# DDR3B.net
KiCad netlist of a schematic drawn in Altium Designer
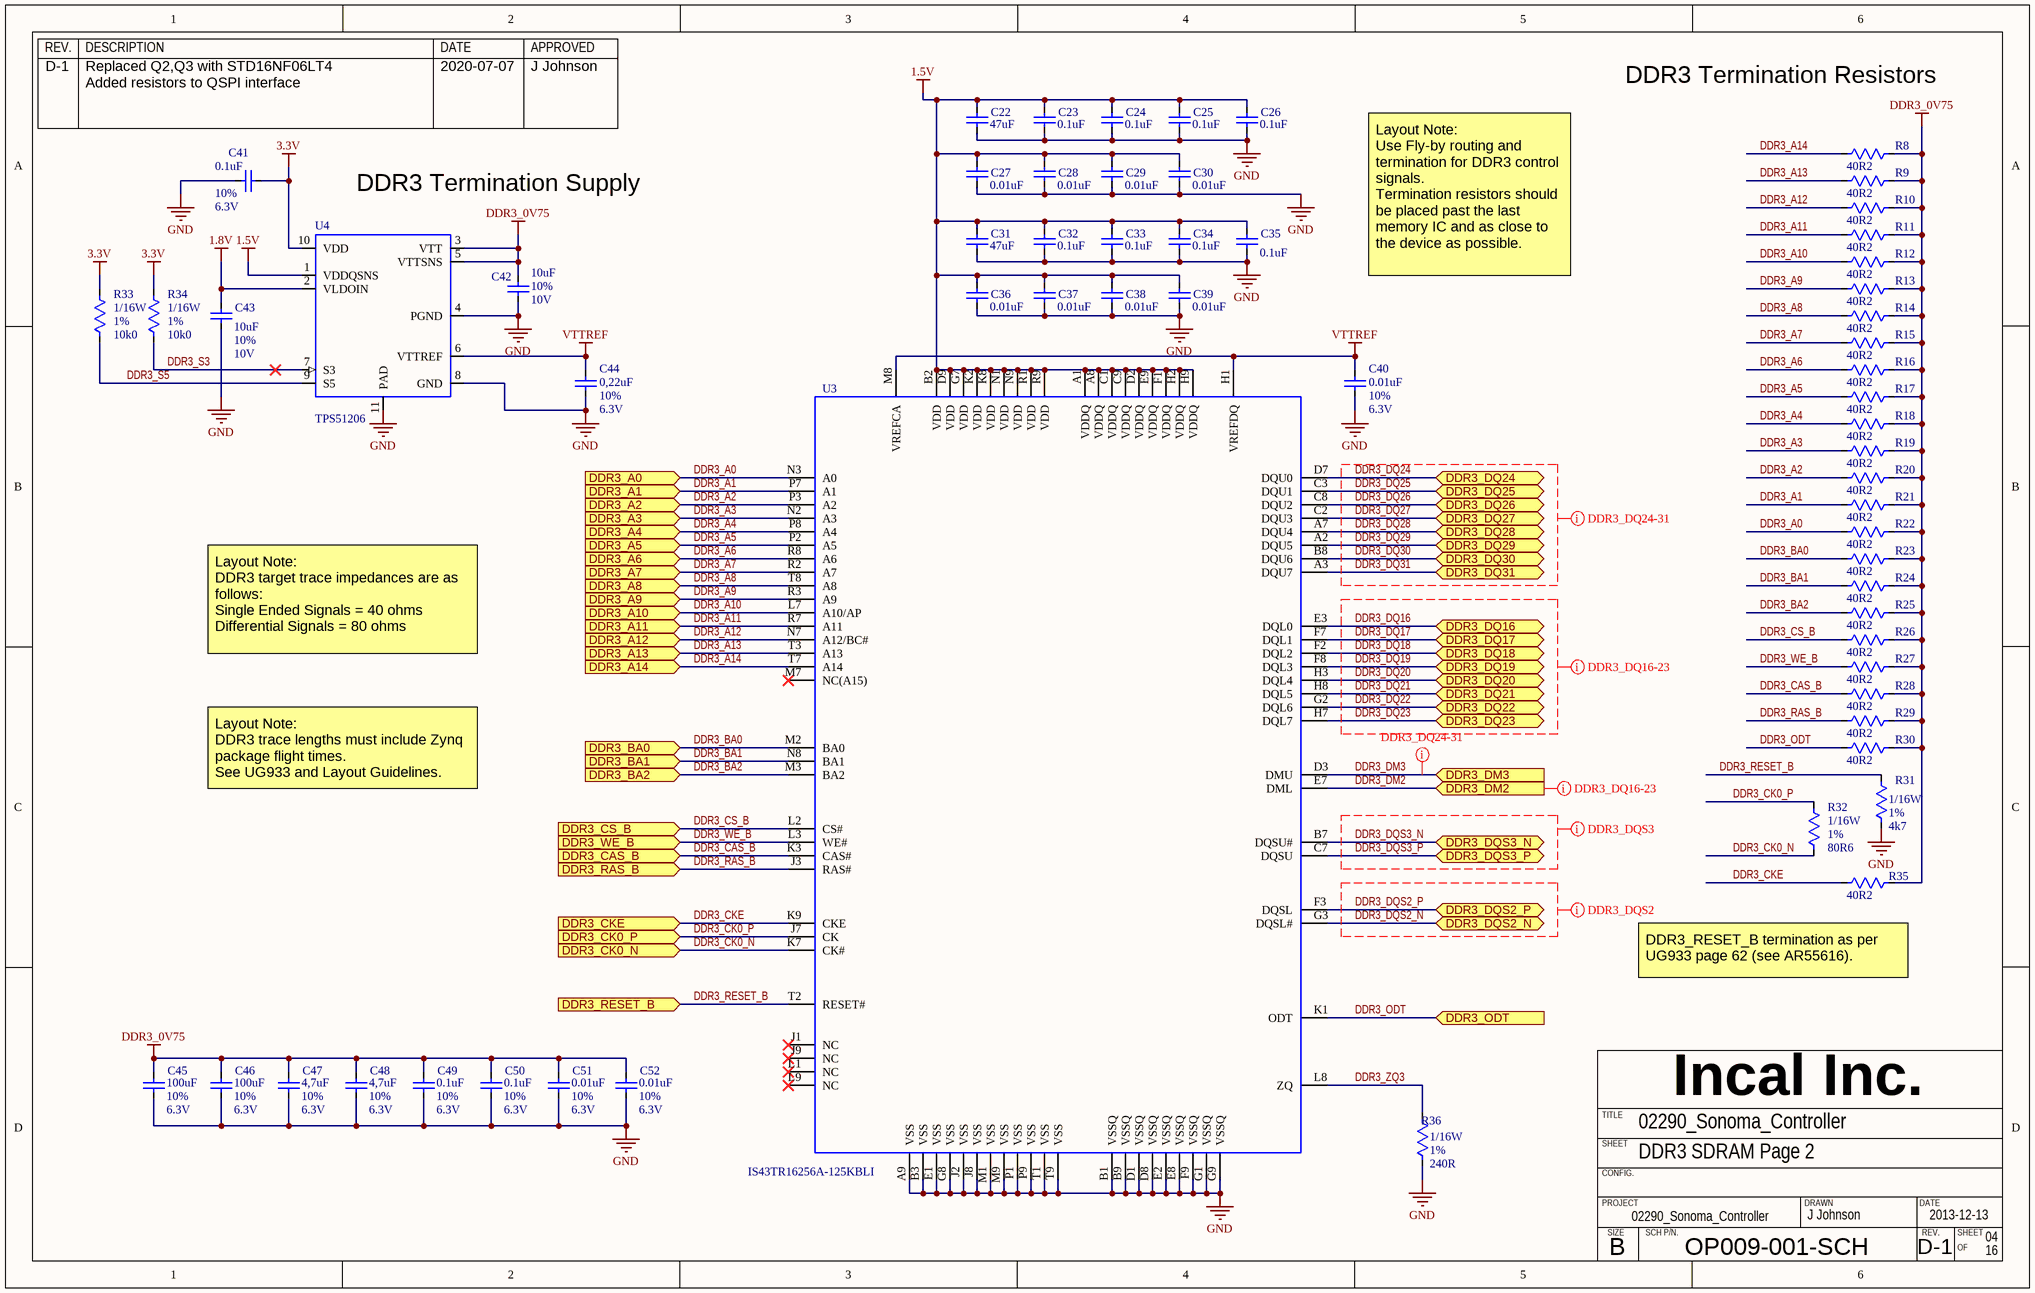
[diagram p0: DDR3B.SchDoc]

(export (version "E")
  (design (tool "Eeschema 10.0.6"))
  (components
    (comp (ref "C22")
      (value "47uF")
      (footprint "CAPC2013X125N")
      (description "Capacitor ceramic, X5R, 47uF, 6.3V, 20%, -55 to +85 C,")
      (fields (field (name "TOLERANCE") "20%") (field (name "VOLTAGE") "6.3V"))
      (libsource (lib "parts") (part "CAPACITOR_NP_TYPE1"))
    )
    (comp (ref "C23")
      (value "0.1uF")
      (footprint "CAPC0603X33N")
      (description "Capacitor ceramic, X5R, 0.1uF, 6.3V, 10%, -55 to +125 C, EIA0201")
      (fields (field (name "TOLERANCE") "10%") (field (name "VOLTAGE") "6.3V"))
      (libsource (lib "parts") (part "CAPACITOR_NP_TYPE1"))
    )
    (comp (ref "C24")
      (value "0.1uF")
      (footprint "CAPC0603X33N")
      (description "Capacitor ceramic, X5R, 0.1uF, 6.3V, 10%, -55 to +125 C, EIA0201")
      (fields (field (name "TOLERANCE") "10%") (field (name "VOLTAGE") "6.3V"))
      (libsource (lib "parts") (part "CAPACITOR_NP_TYPE1"))
    )
    (comp (ref "C25")
      (value "0.1uF")
      (footprint "CAPC0603X33N")
      (description "Capacitor ceramic, X5R, 0.1uF, 6.3V, 10%, -55 to +125 C, EIA0201")
      (fields (field (name "TOLERANCE") "10%") (field (name "VOLTAGE") "6.3V"))
      (libsource (lib "parts") (part "CAPACITOR_NP_TYPE1"))
    )
    (comp (ref "C26")
      (value "0.1uF")
      (footprint "CAPC0603X33N")
      (description "Capacitor ceramic, X5R, 0.1uF, 6.3V, 10%, -55 to +125 C, EIA0201")
      (fields (field (name "TOLERANCE") "10%") (field (name "VOLTAGE") "6.3V"))
      (libsource (lib "parts") (part "CAPACITOR_NP_TYPE1"))
    )
    (comp (ref "C27")
      (value "0.01uF")
      (footprint "CAPC0603X33N")
      (description "Capacitor ceramic, X5R, 0.01uF, 6.3V, 10%, -55 to +125 C, EIA0201")
      (fields (field (name "TOLERANCE") "10%") (field (name "VOLTAGE") "6.3V"))
      (libsource (lib "parts") (part "CAPACITOR_NP_TYPE1"))
    )
    (comp (ref "C28")
      (value "0.01uF")
      (footprint "CAPC0603X33N")
      (description "Capacitor ceramic, X5R, 0.01uF, 6.3V, 10%, -55 to +125 C, EIA0201")
      (fields (field (name "TOLERANCE") "10%") (field (name "VOLTAGE") "6.3V"))
      (libsource (lib "parts") (part "CAPACITOR_NP_TYPE1"))
    )
    (comp (ref "C29")
      (value "0.01uF")
      (footprint "CAPC0603X33N")
      (description "Capacitor ceramic, X5R, 0.01uF, 6.3V, 10%, -55 to +125 C, EIA0201")
      (fields (field (name "TOLERANCE") "10%") (field (name "VOLTAGE") "6.3V"))
      (libsource (lib "parts") (part "CAPACITOR_NP_TYPE1"))
    )
    (comp (ref "C30")
      (value "0.01uF")
      (footprint "CAPC0603X33N")
      (description "Capacitor ceramic, X5R, 0.01uF, 6.3V, 10%, -55 to +125 C, EIA0201")
      (fields (field (name "TOLERANCE") "10%") (field (name "VOLTAGE") "6.3V"))
      (libsource (lib "parts") (part "CAPACITOR_NP_TYPE1"))
    )
    (comp (ref "C31")
      (value "47uF")
      (footprint "CAPC2013X125N")
      (description "Capacitor ceramic, X5R, 47uF, 6.3V, 20%, -55 to +85 C,")
      (fields (field (name "TOLERANCE") "20%") (field (name "VOLTAGE") "6.3V"))
      (libsource (lib "parts") (part "CAPACITOR_NP_TYPE1"))
    )
    (comp (ref "C32")
      (value "0.1uF")
      (footprint "CAPC0603X33N")
      (description "Capacitor ceramic, X5R, 0.1uF, 6.3V, 10%, -55 to +125 C, EIA0201")
      (fields (field (name "TOLERANCE") "10%") (field (name "VOLTAGE") "6.3V"))
      (libsource (lib "parts") (part "CAPACITOR_NP_TYPE1"))
    )
    (comp (ref "C33")
      (value "0.1uF")
      (footprint "CAPC0603X33N")
      (description "Capacitor ceramic, X5R, 0.1uF, 6.3V, 10%, -55 to +125 C, EIA0201")
      (fields (field (name "TOLERANCE") "10%") (field (name "VOLTAGE") "6.3V"))
      (libsource (lib "parts") (part "CAPACITOR_NP_TYPE1"))
    )
    (comp (ref "C34")
      (value "0.1uF")
      (footprint "CAPC0603X33N")
      (description "Capacitor ceramic, X5R, 0.1uF, 6.3V, 10%, -55 to +125 C, EIA0201")
      (fields (field (name "TOLERANCE") "10%") (field (name "VOLTAGE") "6.3V"))
      (libsource (lib "parts") (part "CAPACITOR_NP_TYPE1"))
    )
    (comp (ref "C35")
      (value "0.1uF")
      (footprint "CAPC0603X33N")
      (description "Capacitor ceramic, X5R, 0.1uF, 6.3V, 10%, -55 to +125 C, EIA0201")
      (fields (field (name "TOLERANCE") "10%") (field (name "VOLTAGE") "6.3V"))
      (libsource (lib "parts") (part "CAPACITOR_NP_TYPE1"))
    )
    (comp (ref "C36")
      (value "0.01uF")
      (footprint "CAPC0603X33N")
      (description "Capacitor ceramic, X5R, 0.01uF, 6.3V, 10%, -55 to +125 C, EIA0201")
      (fields (field (name "TOLERANCE") "10%") (field (name "VOLTAGE") "6.3V"))
      (libsource (lib "parts") (part "CAPACITOR_NP_TYPE1"))
    )
    (comp (ref "C37")
      (value "0.01uF")
      (footprint "CAPC0603X33N")
      (description "Capacitor ceramic, X5R, 0.01uF, 6.3V, 10%, -55 to +125 C, EIA0201")
      (fields (field (name "TOLERANCE") "10%") (field (name "VOLTAGE") "6.3V"))
      (libsource (lib "parts") (part "CAPACITOR_NP_TYPE1"))
    )
    (comp (ref "C38")
      (value "0.01uF")
      (footprint "CAPC0603X33N")
      (description "Capacitor ceramic, X5R, 0.01uF, 6.3V, 10%, -55 to +125 C, EIA0201")
      (fields (field (name "TOLERANCE") "10%") (field (name "VOLTAGE") "6.3V"))
      (libsource (lib "parts") (part "CAPACITOR_NP_TYPE1"))
    )
    (comp (ref "C39")
      (value "0.01uF")
      (footprint "CAPC0603X33N")
      (description "Capacitor ceramic, X5R, 0.01uF, 6.3V, 10%, -55 to +125 C, EIA0201")
      (fields (field (name "TOLERANCE") "10%") (field (name "VOLTAGE") "6.3V"))
      (libsource (lib "parts") (part "CAPACITOR_NP_TYPE1"))
    )
    (comp (ref "C40")
      (value "0.01uF")
      (footprint "CAPC0603X33N")
      (description "Capacitor ceramic, X5R, 0.01uF, 6.3V, 10%, -55 to +125 C, EIA0201")
      (fields
        (field (name "TOLERANCE") "10%")
        (field (name "VOLTAGE") "6.3V")
        (field (name "Comment") "CAPACITOR_NP_TYPE1")
      )
      (libsource (lib "parts") (part "CAPACITOR_NP_TYPE1"))
    )
    (comp (ref "C41")
      (value "0.1uF")
      (footprint "CAPC0603X33N")
      (description "Capacitor ceramic, X5R, 0.1uF, 6.3V, 10%, -55 to +125 C, EIA0201")
      (fields
        (field (name "TOLERANCE") "10%")
        (field (name "VOLTAGE") "6.3V")
        (field (name "Comment") "CAPACITOR_NP_TYPE1")
      )
      (libsource (lib "parts") (part "CAPACITOR_NP_TYPE1"))
    )
    (comp (ref "C42")
      (value "10uF")
      (footprint "CAPC1608X38N")
      (description "Capacitor ceramic, X5R, 10uF, 10V, 10%, -55 to +85 C, EIA0603")
      (fields
        (field (name "TOLERANCE") "10%")
        (field (name "VOLTAGE") "10V")
        (field (name "Comment") "CAPACITOR_NP_TYPE1")
      )
      (libsource (lib "parts") (part "CAPACITOR_NP_TYPE1"))
    )
    (comp (ref "C43")
      (value "10uF")
      (footprint "CAPC1608X38N")
      (description "Capacitor ceramic, X5R, 10uF, 10V, 10%, -55 to +85 C, EIA0603")
      (fields
        (field (name "TOLERANCE") "10%")
        (field (name "VOLTAGE") "10V")
        (field (name "Comment") "CAPACITOR_NP_TYPE1")
      )
      (libsource (lib "parts") (part "CAPACITOR_NP_TYPE1"))
    )
    (comp (ref "C44")
      (value "0,22uF")
      (footprint "CAPC1005X55N")
      (description "Capacitor ceramic, X5R, 0.22uF, 6.3V, 10%, -55 to +85 C, EIA0402")
      (fields
        (field (name "TOLERANCE") "10%")
        (field (name "VOLTAGE") "6.3V")
        (field (name "Comment") "CAPACITOR_NP_TYPE1")
      )
      (libsource (lib "parts") (part "CAPACITOR_NP_TYPE1"))
    )
    (comp (ref "C45")
      (value "100uF")
      (footprint "CAPC3225X250N")
      (description "Capacitor ceramic, X5R, 100uF, 6.3V, 10%, -55 to +85 C, EIA1210")
      (fields
        (field (name "TOLERANCE") "10%")
        (field (name "VOLTAGE") "6.3V")
        (field (name "Comment") "CAPACITOR_NP_TYPE1")
      )
      (libsource (lib "parts") (part "CAPACITOR_NP_TYPE1"))
    )
    (comp (ref "C46")
      (value "100uF")
      (footprint "CAPC3225X250N")
      (description "Capacitor ceramic, X5R, 100uF, 6.3V, 10%, -55 to +85 C, EIA1210")
      (fields
        (field (name "TOLERANCE") "10%")
        (field (name "VOLTAGE") "6.3V")
        (field (name "Comment") "CAPACITOR_NP_TYPE1")
      )
      (libsource (lib "parts") (part "CAPACITOR_NP_TYPE1"))
    )
    (comp (ref "C47")
      (value "4,7uF")
      (footprint "CAPC1005X33N")
      (description "Capacitor ceramic, X5R, 4,7uF, 6.3V, 10%, -55 to +85 C, EIA0402")
      (fields
        (field (name "TOLERANCE") "10%")
        (field (name "VOLTAGE") "6.3V")
        (field (name "Comment") "CAPACITOR_NP_TYPE1")
      )
      (libsource (lib "parts") (part "CAPACITOR_NP_TYPE1"))
    )
    (comp (ref "C48")
      (value "4,7uF")
      (footprint "CAPC1005X33N")
      (description "Capacitor ceramic, X5R, 4,7uF, 6.3V, 10%, -55 to +85 C, EIA0402")
      (fields
        (field (name "TOLERANCE") "10%")
        (field (name "VOLTAGE") "6.3V")
        (field (name "Comment") "CAPACITOR_NP_TYPE1")
      )
      (libsource (lib "parts") (part "CAPACITOR_NP_TYPE1"))
    )
    (comp (ref "C49")
      (value "0.1uF")
      (footprint "CAPC0603X33N")
      (description "Capacitor ceramic, X5R, 0.1uF, 6.3V, 10%, -55 to +125 C, EIA0201")
      (fields
        (field (name "TOLERANCE") "10%")
        (field (name "VOLTAGE") "6.3V")
        (field (name "Comment") "CAPACITOR_NP_TYPE1")
      )
      (libsource (lib "parts") (part "CAPACITOR_NP_TYPE1"))
    )
    (comp (ref "C50")
      (value "0.1uF")
      (footprint "CAPC0603X33N")
      (description "Capacitor ceramic, X5R, 0.1uF, 6.3V, 10%, -55 to +125 C, EIA0201")
      (fields
        (field (name "TOLERANCE") "10%")
        (field (name "VOLTAGE") "6.3V")
        (field (name "Comment") "CAPACITOR_NP_TYPE1")
      )
      (libsource (lib "parts") (part "CAPACITOR_NP_TYPE1"))
    )
    (comp (ref "C51")
      (value "0.01uF")
      (footprint "CAPC0603X33N")
      (description "Capacitor ceramic, X5R, 0.01uF, 6.3V, 10%, -55 to +125 C, EIA0201")
      (fields
        (field (name "TOLERANCE") "10%")
        (field (name "VOLTAGE") "6.3V")
        (field (name "Comment") "CAPACITOR_NP_TYPE1")
      )
      (libsource (lib "parts") (part "CAPACITOR_NP_TYPE1"))
    )
    (comp (ref "C52")
      (value "0.01uF")
      (footprint "CAPC0603X33N")
      (description "Capacitor ceramic, X5R, 0.01uF, 6.3V, 10%, -55 to +125 C, EIA0201")
      (fields
        (field (name "TOLERANCE") "10%")
        (field (name "VOLTAGE") "6.3V")
        (field (name "Comment") "CAPACITOR_NP_TYPE1")
      )
      (libsource (lib "parts") (part "CAPACITOR_NP_TYPE1"))
    )
    (comp (ref "R8")
      (value "40R2")
      (footprint "RESC1005X33N")
      (description "Resistor, 40R2, 1/16W, 1%, -50 to +155 C, EIA0402, EIA(M)1005")
      (fields (field (name "VOLTAGE") "50V") (field (name "POWER") "1/16W"))
      (libsource (lib "parts") (part "RESISTOR_TYPE1"))
    )
    (comp (ref "R9")
      (value "40R2")
      (footprint "RESC1005X33N")
      (description "Resistor, 40R2, 1/16W, 1%, -50 to +155 C, EIA0402, EIA(M)1005")
      (fields (field (name "VOLTAGE") "50V") (field (name "POWER") "1/16W"))
      (libsource (lib "parts") (part "RESISTOR_TYPE1"))
    )
    (comp (ref "R10")
      (value "40R2")
      (footprint "RESC1005X33N")
      (description "Resistor, 40R2, 1/16W, 1%, -50 to +155 C, EIA0402, EIA(M)1005")
      (fields (field (name "VOLTAGE") "50V") (field (name "POWER") "1/16W"))
      (libsource (lib "parts") (part "RESISTOR_TYPE1"))
    )
    (comp (ref "R11")
      (value "40R2")
      (footprint "RESC1005X33N")
      (description "Resistor, 40R2, 1/16W, 1%, -50 to +155 C, EIA0402, EIA(M)1005")
      (fields (field (name "VOLTAGE") "50V") (field (name "POWER") "1/16W"))
      (libsource (lib "parts") (part "RESISTOR_TYPE1"))
    )
    (comp (ref "R12")
      (value "40R2")
      (footprint "RESC1005X33N")
      (description "Resistor, 40R2, 1/16W, 1%, -50 to +155 C, EIA0402, EIA(M)1005")
      (fields (field (name "VOLTAGE") "50V") (field (name "POWER") "1/16W"))
      (libsource (lib "parts") (part "RESISTOR_TYPE1"))
    )
    (comp (ref "R13")
      (value "40R2")
      (footprint "RESC1005X33N")
      (description "Resistor, 40R2, 1/16W, 1%, -50 to +155 C, EIA0402, EIA(M)1005")
      (fields (field (name "VOLTAGE") "50V") (field (name "POWER") "1/16W"))
      (libsource (lib "parts") (part "RESISTOR_TYPE1"))
    )
    (comp (ref "R14")
      (value "40R2")
      (footprint "RESC1005X33N")
      (description "Resistor, 40R2, 1/16W, 1%, -50 to +155 C, EIA0402, EIA(M)1005")
      (fields (field (name "VOLTAGE") "50V") (field (name "POWER") "1/16W"))
      (libsource (lib "parts") (part "RESISTOR_TYPE1"))
    )
    (comp (ref "R15")
      (value "40R2")
      (footprint "RESC1005X33N")
      (description "Resistor, 40R2, 1/16W, 1%, -50 to +155 C, EIA0402, EIA(M)1005")
      (fields (field (name "VOLTAGE") "50V") (field (name "POWER") "1/16W"))
      (libsource (lib "parts") (part "RESISTOR_TYPE1"))
    )
    (comp (ref "R16")
      (value "40R2")
      (footprint "RESC1005X33N")
      (description "Resistor, 40R2, 1/16W, 1%, -50 to +155 C, EIA0402, EIA(M)1005")
      (fields (field (name "VOLTAGE") "50V") (field (name "POWER") "1/16W"))
      (libsource (lib "parts") (part "RESISTOR_TYPE1"))
    )
    (comp (ref "R17")
      (value "40R2")
      (footprint "RESC1005X33N")
      (description "Resistor, 40R2, 1/16W, 1%, -50 to +155 C, EIA0402, EIA(M)1005")
      (fields (field (name "VOLTAGE") "50V") (field (name "POWER") "1/16W"))
      (libsource (lib "parts") (part "RESISTOR_TYPE1"))
    )
    (comp (ref "R18")
      (value "40R2")
      (footprint "RESC1005X33N")
      (description "Resistor, 40R2, 1/16W, 1%, -50 to +155 C, EIA0402, EIA(M)1005")
      (fields (field (name "VOLTAGE") "50V") (field (name "POWER") "1/16W"))
      (libsource (lib "parts") (part "RESISTOR_TYPE1"))
    )
    (comp (ref "R19")
      (value "40R2")
      (footprint "RESC1005X33N")
      (description "Resistor, 40R2, 1/16W, 1%, -50 to +155 C, EIA0402, EIA(M)1005")
      (fields (field (name "VOLTAGE") "50V") (field (name "POWER") "1/16W"))
      (libsource (lib "parts") (part "RESISTOR_TYPE1"))
    )
    (comp (ref "R20")
      (value "40R2")
      (footprint "RESC1005X33N")
      (description "Resistor, 40R2, 1/16W, 1%, -50 to +155 C, EIA0402, EIA(M)1005")
      (fields (field (name "VOLTAGE") "50V") (field (name "POWER") "1/16W"))
      (libsource (lib "parts") (part "RESISTOR_TYPE1"))
    )
    (comp (ref "R21")
      (value "40R2")
      (footprint "RESC1005X33N")
      (description "Resistor, 40R2, 1/16W, 1%, -50 to +155 C, EIA0402, EIA(M)1005")
      (fields (field (name "VOLTAGE") "50V") (field (name "POWER") "1/16W"))
      (libsource (lib "parts") (part "RESISTOR_TYPE1"))
    )
    (comp (ref "R22")
      (value "40R2")
      (footprint "RESC1005X33N")
      (description "Resistor, 40R2, 1/16W, 1%, -50 to +155 C, EIA0402, EIA(M)1005")
      (fields (field (name "VOLTAGE") "50V") (field (name "POWER") "1/16W"))
      (libsource (lib "parts") (part "RESISTOR_TYPE1"))
    )
    (comp (ref "R23")
      (value "40R2")
      (footprint "RESC1005X33N")
      (description "Resistor, 40R2, 1/16W, 1%, -50 to +155 C, EIA0402, EIA(M)1005")
      (fields (field (name "VOLTAGE") "50V") (field (name "POWER") "1/16W"))
      (libsource (lib "parts") (part "RESISTOR_TYPE1"))
    )
    (comp (ref "R24")
      (value "40R2")
      (footprint "RESC1005X33N")
      (description "Resistor, 40R2, 1/16W, 1%, -50 to +155 C, EIA0402, EIA(M)1005")
      (fields (field (name "VOLTAGE") "50V") (field (name "POWER") "1/16W"))
      (libsource (lib "parts") (part "RESISTOR_TYPE1"))
    )
    (comp (ref "R25")
      (value "40R2")
      (footprint "RESC1005X33N")
      (description "Resistor, 40R2, 1/16W, 1%, -50 to +155 C, EIA0402, EIA(M)1005")
      (fields (field (name "VOLTAGE") "50V") (field (name "POWER") "1/16W"))
      (libsource (lib "parts") (part "RESISTOR_TYPE1"))
    )
    (comp (ref "R26")
      (value "40R2")
      (footprint "RESC1005X33N")
      (description "Resistor, 40R2, 1/16W, 1%, -50 to +155 C, EIA0402, EIA(M)1005")
      (fields (field (name "VOLTAGE") "50V") (field (name "POWER") "1/16W"))
      (libsource (lib "parts") (part "RESISTOR_TYPE1"))
    )
    (comp (ref "R27")
      (value "40R2")
      (footprint "RESC1005X33N")
      (description "Resistor, 40R2, 1/16W, 1%, -50 to +155 C, EIA0402, EIA(M)1005")
      (fields (field (name "VOLTAGE") "50V") (field (name "POWER") "1/16W"))
      (libsource (lib "parts") (part "RESISTOR_TYPE1"))
    )
    (comp (ref "R28")
      (value "40R2")
      (footprint "RESC1005X33N")
      (description "Resistor, 40R2, 1/16W, 1%, -50 to +155 C, EIA0402, EIA(M)1005")
      (fields (field (name "VOLTAGE") "50V") (field (name "POWER") "1/16W"))
      (libsource (lib "parts") (part "RESISTOR_TYPE1"))
    )
    (comp (ref "R29")
      (value "40R2")
      (footprint "RESC1005X33N")
      (description "Resistor, 40R2, 1/16W, 1%, -50 to +155 C, EIA0402, EIA(M)1005")
      (fields (field (name "VOLTAGE") "50V") (field (name "POWER") "1/16W"))
      (libsource (lib "parts") (part "RESISTOR_TYPE1"))
    )
    (comp (ref "R30")
      (value "40R2")
      (footprint "RESC1005X33N")
      (description "Resistor, 40R2, 1/16W, 1%, -50 to +155 C, EIA0402, EIA(M)1005")
      (fields (field (name "VOLTAGE") "50V") (field (name "POWER") "1/16W"))
      (libsource (lib "parts") (part "RESISTOR_TYPE1"))
    )
    (comp (ref "R31")
      (value "4k7")
      (footprint "RESC1005X33N")
      (description "Resistor, 4k7, 1/16W, 1%, -55 to +155 C, EIA0402")
      (fields (field (name "VOLTAGE") "50V") (field (name "POWER") "1/16W") (field (name "TOLERANCE") "1%"))
      (libsource (lib "parts") (part "RESISTOR_TYPE1"))
    )
    (comp (ref "R32")
      (value "80R6")
      (footprint "RESC1005X33N")
      (description "Resistor, 80R6, 1/16W, 1%, -50 to +155 C, EIA0402, EIA(M)1005")
      (fields (field (name "VOLTAGE") "50V") (field (name "POWER") "1/16W") (field (name "TOLERANCE") "1%"))
      (libsource (lib "parts") (part "RESISTOR_TYPE1"))
    )
    (comp (ref "R33")
      (value "10k0")
      (footprint "RESC1005X33N")
      (description "Resistor, 10k0, 1/16W, 1%, -55 to +155 C, EIA0402")
      (fields (field (name "VOLTAGE") "50V") (field (name "POWER") "1/16W") (field (name "TOLERANCE") "1%"))
      (libsource (lib "parts") (part "RESISTOR_TYPE1"))
    )
    (comp (ref "R34")
      (value "10k0")
      (footprint "RESC1005X33N")
      (description "Resistor, 10k0, 1/16W, 1%, -55 to +155 C, EIA0402")
      (fields (field (name "VOLTAGE") "50V") (field (name "POWER") "1/16W") (field (name "TOLERANCE") "1%"))
      (libsource (lib "parts") (part "RESISTOR_TYPE1"))
    )
    (comp (ref "R35")
      (value "40R2")
      (footprint "RESC1005X33N")
      (description "Resistor, 40R2, 1/16W, 1%, -50 to +155 C, EIA0402, EIA(M)1005")
      (fields (field (name "VOLTAGE") "50V") (field (name "POWER") "1/16W"))
      (libsource (lib "parts") (part "RESISTOR_TYPE1"))
    )
    (comp (ref "R36")
      (value "240R")
      (footprint "RESC1005X33N")
      (description "Resistor, 240R, 1/16W, 1%, -50 to +155 C, EIA0402, EIA(M)1005")
      (fields (field (name "VOLTAGE") "50V") (field (name "POWER") "1/16W") (field (name "TOLERANCE") "1%"))
      (libsource (lib "parts") (part "RESISTOR_TYPE1"))
    )
    (comp (ref "U3")
      (value "IS43TR16256A-125KBLI")
      (footprint "BGA96C80P6X16_900X1300X120")
      (description "DDR3 SDRAM, 512Mx8, 256Mx16 4Gb")
      (libsource (lib "parts") (part "IS43TR16256A-125KBLI"))
    )
    (comp (ref "U4")
      (value "TPS51206")
      (footprint "DFN40P200X200X75-11N")
      (description "DDR Termination Regulator, -40 to +85 C")
      (fields (field (name "VOLTAGE") "3.3V or 5V"))
      (libsource (lib "parts") (part "TPS51206"))
    )
  )
  (nets
    (net (code "1") (name "/DDR3_A0") (class "Default")
      (node (ref "R22") (pin "2") (pinfunction "2_2") (pintype "passive"))
      (node (ref "U3") (pin "N3") (pinfunction "A0_N3") (pintype "passive"))
    )
    (net (code "2") (name "/DDR3_A1") (class "Default")
      (node (ref "R21") (pin "2") (pinfunction "2_2") (pintype "passive"))
      (node (ref "U3") (pin "P7") (pinfunction "A1_P7") (pintype "passive"))
    )
    (net (code "3") (name "/DDR3_A2") (class "Default")
      (node (ref "R20") (pin "2") (pinfunction "2_2") (pintype "passive"))
      (node (ref "U3") (pin "P3") (pinfunction "A2_P3") (pintype "passive"))
    )
    (net (code "4") (name "/DDR3_A3") (class "Default")
      (node (ref "R19") (pin "2") (pinfunction "2_2") (pintype "passive"))
      (node (ref "U3") (pin "N2") (pinfunction "A3_N2") (pintype "passive"))
    )
    (net (code "5") (name "/DDR3_A4") (class "Default")
      (node (ref "R18") (pin "2") (pinfunction "2_2") (pintype "passive"))
      (node (ref "U3") (pin "P8") (pinfunction "A4_P8") (pintype "passive"))
    )
    (net (code "6") (name "/DDR3_A5") (class "Default")
      (node (ref "R17") (pin "2") (pinfunction "2_2") (pintype "passive"))
      (node (ref "U3") (pin "P2") (pinfunction "A5_P2") (pintype "passive"))
    )
    (net (code "7") (name "/DDR3_A6") (class "Default")
      (node (ref "R16") (pin "2") (pinfunction "2_2") (pintype "passive"))
      (node (ref "U3") (pin "R8") (pinfunction "A6_R8") (pintype "passive"))
    )
    (net (code "8") (name "/DDR3_A7") (class "Default")
      (node (ref "R15") (pin "2") (pinfunction "2_2") (pintype "passive"))
      (node (ref "U3") (pin "R2") (pinfunction "A7_R2") (pintype "passive"))
    )
    (net (code "9") (name "/DDR3_A8") (class "Default")
      (node (ref "R14") (pin "2") (pinfunction "2_2") (pintype "passive"))
      (node (ref "U3") (pin "T8") (pinfunction "A8_T8") (pintype "passive"))
    )
    (net (code "10") (name "/DDR3_A9") (class "Default")
      (node (ref "R13") (pin "2") (pinfunction "2_2") (pintype "passive"))
      (node (ref "U3") (pin "R3") (pinfunction "A9_R3") (pintype "passive"))
    )
    (net (code "11") (name "/DDR3_A10") (class "Default")
      (node (ref "R12") (pin "2") (pinfunction "2_2") (pintype "passive"))
      (node (ref "U3") (pin "L7") (pinfunction "A10/AP_L7") (pintype "passive"))
    )
    (net (code "12") (name "/DDR3_A11") (class "Default")
      (node (ref "R11") (pin "2") (pinfunction "2_2") (pintype "passive"))
      (node (ref "U3") (pin "R7") (pinfunction "A11_R7") (pintype "passive"))
    )
    (net (code "13") (name "/DDR3_A12") (class "Default")
      (node (ref "R10") (pin "2") (pinfunction "2_2") (pintype "passive"))
      (node (ref "U3") (pin "N7") (pinfunction "A12/BC#_N7") (pintype "passive"))
    )
    (net (code "14") (name "/DDR3_A13") (class "Default")
      (node (ref "R9") (pin "2") (pinfunction "2_2") (pintype "passive"))
      (node (ref "U3") (pin "T3") (pinfunction "A13_T3") (pintype "passive"))
    )
    (net (code "15") (name "/DDR3_A14") (class "Default")
      (node (ref "R8") (pin "2") (pinfunction "2_2") (pintype "passive"))
      (node (ref "U3") (pin "T7") (pinfunction "A14_T7") (pintype "passive"))
    )
    (net (code "16") (name "/DDR3_BA0") (class "Default")
      (node (ref "R23") (pin "2") (pinfunction "2_2") (pintype "passive"))
      (node (ref "U3") (pin "M2") (pinfunction "BA0_M2") (pintype "passive"))
    )
    (net (code "17") (name "/DDR3_BA1") (class "Default")
      (node (ref "R24") (pin "2") (pinfunction "2_2") (pintype "passive"))
      (node (ref "U3") (pin "N8") (pinfunction "BA1_N8") (pintype "passive"))
    )
    (net (code "18") (name "/DDR3_BA2") (class "Default")
      (node (ref "R25") (pin "2") (pinfunction "2_2") (pintype "passive"))
      (node (ref "U3") (pin "M3") (pinfunction "BA2_M3") (pintype "passive"))
    )
    (net (code "19") (name "/DDR3_CAS_B") (class "Default")
      (node (ref "R28") (pin "2") (pinfunction "2_2") (pintype "passive"))
      (node (ref "U3") (pin "K3") (pinfunction "CAS#_K3") (pintype "passive"))
    )
    (net (code "20") (name "/DDR3_CK0_N") (class "Default")
      (node (ref "R32") (pin "1") (pinfunction "1_1") (pintype "passive"))
      (node (ref "U3") (pin "K7") (pinfunction "CK#_K7") (pintype "passive"))
    )
    (net (code "21") (name "/DDR3_CK0_P") (class "Default")
      (node (ref "R32") (pin "2") (pinfunction "2_2") (pintype "passive"))
      (node (ref "U3") (pin "J7") (pinfunction "CK_J7") (pintype "passive"))
    )
    (net (code "22") (name "/DDR3_CKE") (class "Default")
      (node (ref "R35") (pin "2") (pinfunction "2_2") (pintype "passive"))
      (node (ref "U3") (pin "K9") (pinfunction "CKE_K9") (pintype "passive"))
    )
    (net (code "23") (name "/DDR3_CS_B") (class "Default")
      (node (ref "R26") (pin "2") (pinfunction "2_2") (pintype "passive"))
      (node (ref "U3") (pin "L2") (pinfunction "CS#_L2") (pintype "passive"))
    )
    (net (code "24") (name "/DDR3_DM2") (class "Default")
      (node (ref "U3") (pin "E7") (pinfunction "DML_E7") (pintype "passive"))
    )
    (net (code "25") (name "/DDR3_DM3") (class "Default")
      (node (ref "U3") (pin "D3") (pinfunction "DMU_D3") (pintype "passive"))
    )
    (net (code "26") (name "/DDR3_DQ16") (class "Default")
      (node (ref "U3") (pin "E3") (pinfunction "DQL0_E3") (pintype "passive"))
    )
    (net (code "27") (name "/DDR3_DQ17") (class "Default")
      (node (ref "U3") (pin "F7") (pinfunction "DQL1_F7") (pintype "passive"))
    )
    (net (code "28") (name "/DDR3_DQ18") (class "Default")
      (node (ref "U3") (pin "F2") (pinfunction "DQL2_F2") (pintype "passive"))
    )
    (net (code "29") (name "/DDR3_DQ19") (class "Default")
      (node (ref "U3") (pin "F8") (pinfunction "DQL3_F8") (pintype "passive"))
    )
    (net (code "30") (name "/DDR3_DQ20") (class "Default")
      (node (ref "U3") (pin "H3") (pinfunction "DQL4_H3") (pintype "passive"))
    )
    (net (code "31") (name "/DDR3_DQ21") (class "Default")
      (node (ref "U3") (pin "H8") (pinfunction "DQL5_H8") (pintype "passive"))
    )
    (net (code "32") (name "/DDR3_DQ22") (class "Default")
      (node (ref "U3") (pin "G2") (pinfunction "DQL6_G2") (pintype "passive"))
    )
    (net (code "33") (name "/DDR3_DQ23") (class "Default")
      (node (ref "U3") (pin "H7") (pinfunction "DQL7_H7") (pintype "passive"))
    )
    (net (code "34") (name "/DDR3_DQ24") (class "Default")
      (node (ref "U3") (pin "D7") (pinfunction "DQU0_D7") (pintype "passive"))
    )
    (net (code "35") (name "/DDR3_DQ25") (class "Default")
      (node (ref "U3") (pin "C3") (pinfunction "DQU1_C3") (pintype "passive"))
    )
    (net (code "36") (name "/DDR3_DQ26") (class "Default")
      (node (ref "U3") (pin "C8") (pinfunction "DQU2_C8") (pintype "passive"))
    )
    (net (code "37") (name "/DDR3_DQ27") (class "Default")
      (node (ref "U3") (pin "C2") (pinfunction "DQU3_C2") (pintype "passive"))
    )
    (net (code "38") (name "/DDR3_DQ28") (class "Default")
      (node (ref "U3") (pin "A7") (pinfunction "DQU4_A7") (pintype "passive"))
    )
    (net (code "39") (name "/DDR3_DQ29") (class "Default")
      (node (ref "U3") (pin "A2") (pinfunction "DQU5_A2") (pintype "passive"))
    )
    (net (code "40") (name "/DDR3_DQ30") (class "Default")
      (node (ref "U3") (pin "B8") (pinfunction "DQU6_B8") (pintype "passive"))
    )
    (net (code "41") (name "/DDR3_DQ31") (class "Default")
      (node (ref "U3") (pin "A3") (pinfunction "DQU7_A3") (pintype "passive"))
    )
    (net (code "42") (name "/DDR3_DQS2_N") (class "Default")
      (node (ref "U3") (pin "G3") (pinfunction "DQSL#_G3") (pintype "passive"))
    )
    (net (code "43") (name "/DDR3_DQS2_P") (class "Default")
      (node (ref "U3") (pin "F3") (pinfunction "DQSL_F3") (pintype "passive"))
    )
    (net (code "44") (name "/DDR3_DQS3_N") (class "Default")
      (node (ref "U3") (pin "B7") (pinfunction "DQSU#_B7") (pintype "passive"))
    )
    (net (code "45") (name "/DDR3_DQS3_P") (class "Default")
      (node (ref "U3") (pin "C7") (pinfunction "DQSU_C7") (pintype "passive"))
    )
    (net (code "46") (name "/DDR3_ODT") (class "Default")
      (node (ref "R30") (pin "2") (pinfunction "2_2") (pintype "passive"))
      (node (ref "U3") (pin "K1") (pinfunction "ODT_K1") (pintype "passive"))
    )
    (net (code "47") (name "/DDR3_RAS_B") (class "Default")
      (node (ref "R29") (pin "2") (pinfunction "2_2") (pintype "passive"))
      (node (ref "U3") (pin "J3") (pinfunction "RAS#_J3") (pintype "passive"))
    )
    (net (code "48") (name "/DDR3_RESET_B") (class "Default")
      (node (ref "R31") (pin "1") (pinfunction "1_1") (pintype "passive"))
      (node (ref "U3") (pin "T2") (pinfunction "RESET#_T2") (pintype "passive"))
    )
    (net (code "49") (name "/DDR3_S3") (class "Default")
      (node (ref "R34") (pin "2") (pinfunction "2_2") (pintype "passive"))
      (node (ref "U4") (pin "7") (pinfunction "S3_7") (pintype "input"))
    )
    (net (code "50") (name "/DDR3_S5") (class "Default")
      (node (ref "R33") (pin "2") (pinfunction "2_2") (pintype "passive"))
      (node (ref "U4") (pin "9") (pinfunction "S5_9") (pintype "passive"))
    )
    (net (code "51") (name "/DDR3_WE_B") (class "Default")
      (node (ref "R27") (pin "2") (pinfunction "2_2") (pintype "passive"))
      (node (ref "U3") (pin "L3") (pinfunction "WE#_L3") (pintype "passive"))
    )
    (net (code "52") (name "/DDR3_ZQ3") (class "Default")
      (node (ref "R36") (pin "2") (pinfunction "2_2") (pintype "passive"))
      (node (ref "U3") (pin "L8") (pinfunction "ZQ_L8") (pintype "passive"))
    )
    (net (code "53") (name "1.5V") (class "Default")
      (node (ref "C22") (pin "1") (pinfunction "1_1") (pintype "passive"))
      (node (ref "C23") (pin "1") (pinfunction "1_1") (pintype "passive"))
      (node (ref "C24") (pin "1") (pinfunction "1_1") (pintype "passive"))
      (node (ref "C25") (pin "1") (pinfunction "1_1") (pintype "passive"))
      (node (ref "C26") (pin "1") (pinfunction "1_1") (pintype "passive"))
      (node (ref "C27") (pin "1") (pinfunction "1_1") (pintype "passive"))
      (node (ref "C28") (pin "1") (pinfunction "1_1") (pintype "passive"))
      (node (ref "C29") (pin "1") (pinfunction "1_1") (pintype "passive"))
      (node (ref "C30") (pin "1") (pinfunction "1_1") (pintype "passive"))
      (node (ref "C31") (pin "1") (pinfunction "1_1") (pintype "passive"))
      (node (ref "C32") (pin "1") (pinfunction "1_1") (pintype "passive"))
      (node (ref "C33") (pin "1") (pinfunction "1_1") (pintype "passive"))
      (node (ref "C34") (pin "1") (pinfunction "1_1") (pintype "passive"))
      (node (ref "C35") (pin "1") (pinfunction "1_1") (pintype "passive"))
      (node (ref "C36") (pin "1") (pinfunction "1_1") (pintype "passive"))
      (node (ref "C37") (pin "1") (pinfunction "1_1") (pintype "passive"))
      (node (ref "C38") (pin "1") (pinfunction "1_1") (pintype "passive"))
      (node (ref "C39") (pin "1") (pinfunction "1_1") (pintype "passive"))
      (node (ref "U3") (pin "A1") (pinfunction "VDDQ_A1") (pintype "passive"))
      (node (ref "U3") (pin "A8") (pinfunction "VDDQ_A8") (pintype "passive"))
      (node (ref "U3") (pin "B2") (pinfunction "VDD_B2") (pintype "passive"))
      (node (ref "U3") (pin "C1") (pinfunction "VDDQ_C1") (pintype "passive"))
      (node (ref "U3") (pin "C9") (pinfunction "VDDQ_C9") (pintype "passive"))
      (node (ref "U3") (pin "D2") (pinfunction "VDDQ_D2") (pintype "passive"))
      (node (ref "U3") (pin "D9") (pinfunction "VDD_D9") (pintype "passive"))
      (node (ref "U3") (pin "E9") (pinfunction "VDDQ_E9") (pintype "passive"))
      (node (ref "U3") (pin "F1") (pinfunction "VDDQ_F1") (pintype "passive"))
      (node (ref "U3") (pin "G7") (pinfunction "VDD_G7") (pintype "passive"))
      (node (ref "U3") (pin "H2") (pinfunction "VDDQ_H2") (pintype "passive"))
      (node (ref "U3") (pin "H9") (pinfunction "VDDQ_H9") (pintype "passive"))
      (node (ref "U3") (pin "K2") (pinfunction "VDD_K2") (pintype "passive"))
      (node (ref "U3") (pin "K8") (pinfunction "VDD_K8") (pintype "passive"))
      (node (ref "U3") (pin "N1") (pinfunction "VDD_N1") (pintype "passive"))
      (node (ref "U3") (pin "N9") (pinfunction "VDD_N9") (pintype "passive"))
      (node (ref "U3") (pin "R1") (pinfunction "VDD_R1") (pintype "passive"))
      (node (ref "U3") (pin "R9") (pinfunction "VDD_R9") (pintype "passive"))
      (node (ref "U4") (pin "1") (pinfunction "VDDQSNS_1") (pintype "power_in"))
    )
    (net (code "54") (name "1.8V") (class "Default")
      (node (ref "C43") (pin "1") (pinfunction "1_1") (pintype "passive"))
      (node (ref "U4") (pin "2") (pinfunction "VLDOIN_2") (pintype "power_in"))
    )
    (net (code "55") (name "3.3V") (class "Default")
      (node (ref "C41") (pin "1") (pinfunction "1_1") (pintype "passive"))
      (node (ref "R33") (pin "1") (pinfunction "1_1") (pintype "passive"))
      (node (ref "R34") (pin "1") (pinfunction "1_1") (pintype "passive"))
      (node (ref "U4") (pin "10") (pinfunction "VDD_10") (pintype "power_in"))
    )
    (net (code "56") (name "DDR3_0V75") (class "Default")
      (node (ref "C42") (pin "1") (pinfunction "1_1") (pintype "passive"))
      (node (ref "C45") (pin "1") (pinfunction "1_1") (pintype "passive"))
      (node (ref "C46") (pin "1") (pinfunction "1_1") (pintype "passive"))
      (node (ref "C47") (pin "1") (pinfunction "1_1") (pintype "passive"))
      (node (ref "C48") (pin "1") (pinfunction "1_1") (pintype "passive"))
      (node (ref "C49") (pin "1") (pinfunction "1_1") (pintype "passive"))
      (node (ref "C50") (pin "1") (pinfunction "1_1") (pintype "passive"))
      (node (ref "C51") (pin "1") (pinfunction "1_1") (pintype "passive"))
      (node (ref "C52") (pin "1") (pinfunction "1_1") (pintype "passive"))
      (node (ref "R10") (pin "1") (pinfunction "1_1") (pintype "passive"))
      (node (ref "R11") (pin "1") (pinfunction "1_1") (pintype "passive"))
      (node (ref "R12") (pin "1") (pinfunction "1_1") (pintype "passive"))
      (node (ref "R13") (pin "1") (pinfunction "1_1") (pintype "passive"))
      (node (ref "R14") (pin "1") (pinfunction "1_1") (pintype "passive"))
      (node (ref "R15") (pin "1") (pinfunction "1_1") (pintype "passive"))
      (node (ref "R16") (pin "1") (pinfunction "1_1") (pintype "passive"))
      (node (ref "R17") (pin "1") (pinfunction "1_1") (pintype "passive"))
      (node (ref "R18") (pin "1") (pinfunction "1_1") (pintype "passive"))
      (node (ref "R19") (pin "1") (pinfunction "1_1") (pintype "passive"))
      (node (ref "R20") (pin "1") (pinfunction "1_1") (pintype "passive"))
      (node (ref "R21") (pin "1") (pinfunction "1_1") (pintype "passive"))
      (node (ref "R22") (pin "1") (pinfunction "1_1") (pintype "passive"))
      (node (ref "R23") (pin "1") (pinfunction "1_1") (pintype "passive"))
      (node (ref "R24") (pin "1") (pinfunction "1_1") (pintype "passive"))
      (node (ref "R25") (pin "1") (pinfunction "1_1") (pintype "passive"))
      (node (ref "R26") (pin "1") (pinfunction "1_1") (pintype "passive"))
      (node (ref "R27") (pin "1") (pinfunction "1_1") (pintype "passive"))
      (node (ref "R28") (pin "1") (pinfunction "1_1") (pintype "passive"))
      (node (ref "R29") (pin "1") (pinfunction "1_1") (pintype "passive"))
      (node (ref "R30") (pin "1") (pinfunction "1_1") (pintype "passive"))
      (node (ref "R35") (pin "1") (pinfunction "1_1") (pintype "passive"))
      (node (ref "R8") (pin "1") (pinfunction "1_1") (pintype "passive"))
      (node (ref "R9") (pin "1") (pinfunction "1_1") (pintype "passive"))
      (node (ref "U4") (pin "3") (pinfunction "VTT_3") (pintype "power_in"))
      (node (ref "U4") (pin "5") (pinfunction "VTTSNS_5") (pintype "power_in"))
    )
    (net (code "57") (name "GND") (class "Default")
      (node (ref "C22") (pin "2") (pinfunction "2_2") (pintype "passive"))
      (node (ref "C23") (pin "2") (pinfunction "2_2") (pintype "passive"))
      (node (ref "C24") (pin "2") (pinfunction "2_2") (pintype "passive"))
      (node (ref "C25") (pin "2") (pinfunction "2_2") (pintype "passive"))
      (node (ref "C26") (pin "2") (pinfunction "2_2") (pintype "passive"))
      (node (ref "C27") (pin "2") (pinfunction "2_2") (pintype "passive"))
      (node (ref "C28") (pin "2") (pinfunction "2_2") (pintype "passive"))
      (node (ref "C29") (pin "2") (pinfunction "2_2") (pintype "passive"))
      (node (ref "C30") (pin "2") (pinfunction "2_2") (pintype "passive"))
      (node (ref "C31") (pin "2") (pinfunction "2_2") (pintype "passive"))
      (node (ref "C32") (pin "2") (pinfunction "2_2") (pintype "passive"))
      (node (ref "C33") (pin "2") (pinfunction "2_2") (pintype "passive"))
      (node (ref "C34") (pin "2") (pinfunction "2_2") (pintype "passive"))
      (node (ref "C35") (pin "2") (pinfunction "2_2") (pintype "passive"))
      (node (ref "C36") (pin "2") (pinfunction "2_2") (pintype "passive"))
      (node (ref "C37") (pin "2") (pinfunction "2_2") (pintype "passive"))
      (node (ref "C38") (pin "2") (pinfunction "2_2") (pintype "passive"))
      (node (ref "C39") (pin "2") (pinfunction "2_2") (pintype "passive"))
      (node (ref "C40") (pin "2") (pinfunction "2_2") (pintype "passive"))
      (node (ref "C41") (pin "2") (pinfunction "2_2") (pintype "passive"))
      (node (ref "C42") (pin "2") (pinfunction "2_2") (pintype "passive"))
      (node (ref "C43") (pin "2") (pinfunction "2_2") (pintype "passive"))
      (node (ref "C44") (pin "2") (pinfunction "2_2") (pintype "passive"))
      (node (ref "C45") (pin "2") (pinfunction "2_2") (pintype "passive"))
      (node (ref "C46") (pin "2") (pinfunction "2_2") (pintype "passive"))
      (node (ref "C47") (pin "2") (pinfunction "2_2") (pintype "passive"))
      (node (ref "C48") (pin "2") (pinfunction "2_2") (pintype "passive"))
      (node (ref "C49") (pin "2") (pinfunction "2_2") (pintype "passive"))
      (node (ref "C50") (pin "2") (pinfunction "2_2") (pintype "passive"))
      (node (ref "C51") (pin "2") (pinfunction "2_2") (pintype "passive"))
      (node (ref "C52") (pin "2") (pinfunction "2_2") (pintype "passive"))
      (node (ref "R31") (pin "2") (pinfunction "2_2") (pintype "passive"))
      (node (ref "R36") (pin "1") (pinfunction "1_1") (pintype "passive"))
      (node (ref "U3") (pin "A9") (pinfunction "VSS_A9") (pintype "passive"))
      (node (ref "U3") (pin "B1") (pinfunction "VSSQ_B1") (pintype "passive"))
      (node (ref "U3") (pin "B3") (pinfunction "VSS_B3") (pintype "passive"))
      (node (ref "U3") (pin "B9") (pinfunction "VSSQ_B9") (pintype "passive"))
      (node (ref "U3") (pin "D1") (pinfunction "VSSQ_D1") (pintype "passive"))
      (node (ref "U3") (pin "D8") (pinfunction "VSSQ_D8") (pintype "passive"))
      (node (ref "U3") (pin "E1") (pinfunction "VSS_E1") (pintype "passive"))
      (node (ref "U3") (pin "E2") (pinfunction "VSSQ_E2") (pintype "passive"))
      (node (ref "U3") (pin "E8") (pinfunction "VSSQ_E8") (pintype "passive"))
      (node (ref "U3") (pin "F9") (pinfunction "VSSQ_F9") (pintype "passive"))
      (node (ref "U3") (pin "G1") (pinfunction "VSSQ_G1") (pintype "passive"))
      (node (ref "U3") (pin "G8") (pinfunction "VSS_G8") (pintype "passive"))
      (node (ref "U3") (pin "G9") (pinfunction "VSSQ_G9") (pintype "passive"))
      (node (ref "U3") (pin "J2") (pinfunction "VSS_J2") (pintype "passive"))
      (node (ref "U3") (pin "J8") (pinfunction "VSS_J8") (pintype "passive"))
      (node (ref "U3") (pin "M1") (pinfunction "VSS_M1") (pintype "passive"))
      (node (ref "U3") (pin "M9") (pinfunction "VSS_M9") (pintype "passive"))
      (node (ref "U3") (pin "P1") (pinfunction "VSS_P1") (pintype "passive"))
      (node (ref "U3") (pin "P9") (pinfunction "VSS_P9") (pintype "passive"))
      (node (ref "U3") (pin "T1") (pinfunction "VSS_T1") (pintype "passive"))
      (node (ref "U3") (pin "T9") (pinfunction "VSS_T9") (pintype "passive"))
      (node (ref "U4") (pin "11") (pinfunction "PAD_11") (pintype "power_in"))
      (node (ref "U4") (pin "4") (pinfunction "PGND_4") (pintype "power_in"))
      (node (ref "U4") (pin "8") (pinfunction "GND_8") (pintype "power_in"))
    )
    (net (code "58") (name "VTTREF") (class "Default")
      (node (ref "C40") (pin "1") (pinfunction "1_1") (pintype "passive"))
      (node (ref "C44") (pin "1") (pinfunction "1_1") (pintype "passive"))
      (node (ref "U3") (pin "H1") (pinfunction "VREFDQ_H1") (pintype "passive"))
      (node (ref "U3") (pin "M8") (pinfunction "VREFCA_M8") (pintype "passive"))
      (node (ref "U4") (pin "6") (pinfunction "VTTREF_6") (pintype "power_in"))
    )
    (net (code "59") (name "unconnected-(U3-NC(A15)-PadM7)") (class "Default")
      (node (ref "U3") (pin "M7") (pinfunction "NC(A15)_M7") (pintype "passive+no_connect"))
    )
    (net (code "60") (name "unconnected-(U3-NC-PadJ1)") (class "Default")
      (node (ref "U3") (pin "J1") (pinfunction "NC_J1") (pintype "passive+no_connect"))
    )
    (net (code "61") (name "unconnected-(U3-NC-PadJ9)") (class "Default")
      (node (ref "U3") (pin "J9") (pinfunction "NC_J9") (pintype "passive+no_connect"))
    )
    (net (code "62") (name "unconnected-(U3-NC-PadL1)") (class "Default")
      (node (ref "U3") (pin "L1") (pinfunction "NC_L1") (pintype "passive+no_connect"))
    )
    (net (code "63") (name "unconnected-(U3-NC-PadL9)") (class "Default")
      (node (ref "U3") (pin "L9") (pinfunction "NC_L9") (pintype "passive+no_connect"))
    )
  )
)
